# ProPrj___2025-07-17.net
KiCad netlist of a schematic drawn in EasyEDA Pro
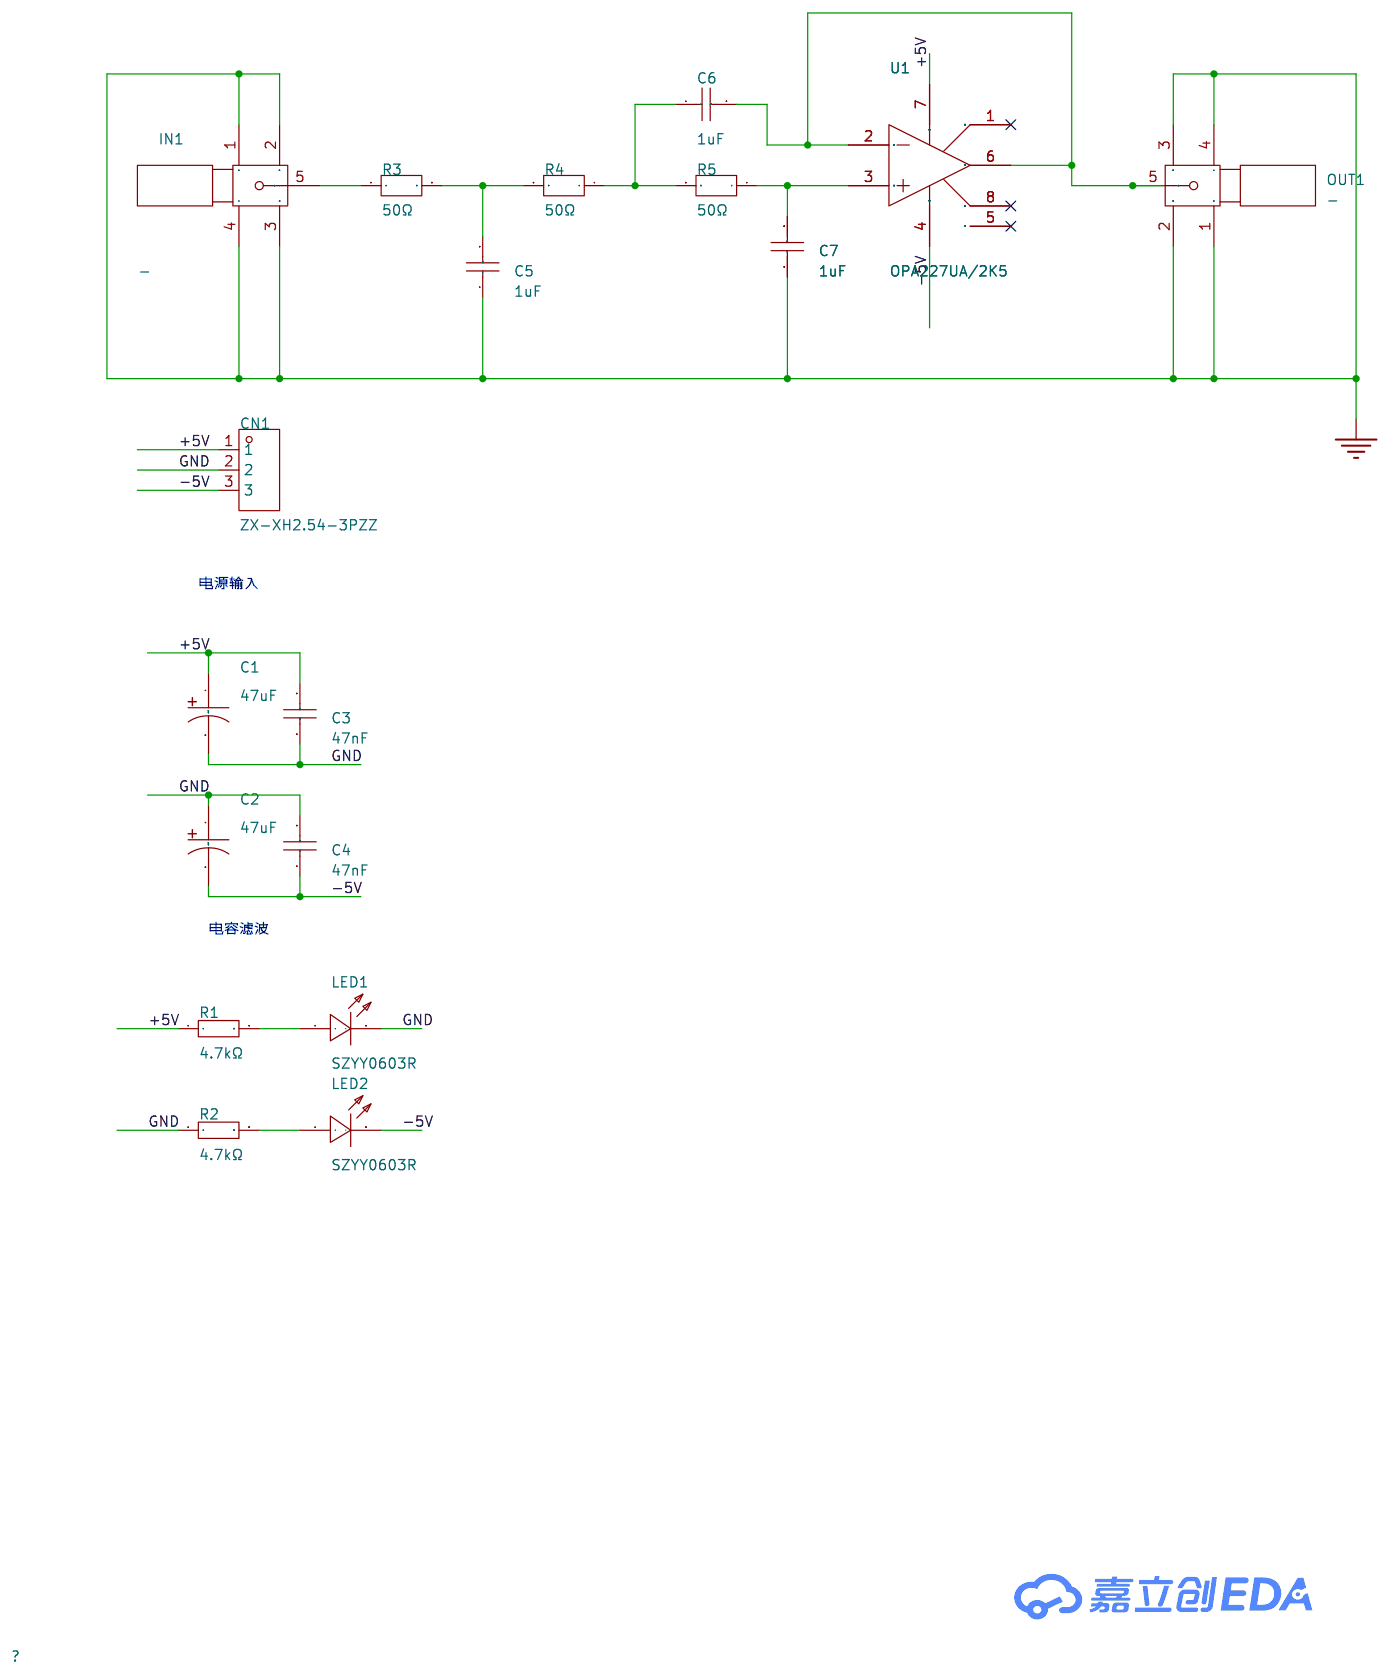
[diagram p0: schematic sheet]

(export (version "E")
  (design (tool "Eeschema 10.0.6"))
  (components
    (comp (ref "C1")
      (value "47uF")
      (footprint "easyedapro:CAP-TH_BD5.0-P2.00-D0.8-FD")
      (description "容值:47uF;精度:±20%;额定电压:25V;纹波电流:250mA@100kHz;等效串联电阻(ESR):300mΩ@100kHz;")
      (fields
        (field (name "Manufacturer Part") "NXB25V47M5*11 2.5TP")
        (field (name "Manufacturer") "SAMYOUNG(韩国三莹)")
      )
      (libsource (lib "easyedapro") (part "NXB25VB47M5*11_2.5TP"))
    )
    (comp (ref "C2")
      (value "47uF")
      (footprint "easyedapro:CAP-TH_BD5.0-P2.00-D0.8-FD")
      (description "容值:47uF;精度:±20%;额定电压:25V;纹波电流:250mA@100kHz;等效串联电阻(ESR):300mΩ@100kHz;")
      (fields
        (field (name "Manufacturer Part") "NXB25V47M5*11 2.5TP")
        (field (name "Manufacturer") "SAMYOUNG(韩国三莹)")
      )
      (libsource (lib "easyedapro") (part "NXB25VB47M5*11_2.5TP"))
    )
    (comp (ref "C3")
      (value "47nF")
      (footprint "easyedapro:C0805")
      (description "容值:47nF;精度:±10%;额定电压:50V;材质(温度系数):X7R;")
      (fields
        (field (name "Manufacturer Part") "CL21B473KBCNNNC")
        (field (name "Manufacturer") "SAMSUNG(三星)")
      )
      (libsource (lib "easyedapro") (part "CL21B473KBCNNNC"))
    )
    (comp (ref "C4")
      (value "47nF")
      (footprint "easyedapro:C0805")
      (description "容值:47nF;精度:±10%;额定电压:50V;材质(温度系数):X7R;")
      (fields
        (field (name "Manufacturer Part") "CL21B473KBCNNNC")
        (field (name "Manufacturer") "SAMSUNG(三星)")
      )
      (libsource (lib "easyedapro") (part "CL21B473KBCNNNC"))
    )
    (comp (ref "C5")
      (value "1uF")
      (footprint "easyedapro:C0805")
      (description "容值:1uF;精度:±10%;额定电压:50V;材质(温度系数):X7R;")
      (fields
        (field (name "Manufacturer Part") "CL21B105KBFNNNE")
        (field (name "Manufacturer") "SAMSUNG(三星)")
      )
      (libsource (lib "easyedapro") (part "CL21B105KBFNNNE"))
    )
    (comp (ref "C6")
      (value "1uF")
      (footprint "easyedapro:C0805")
      (description "容值:1uF;精度:±10%;额定电压:50V;材质(温度系数):X7R;")
      (fields
        (field (name "Manufacturer Part") "CL21B105KBFNNNE")
        (field (name "Manufacturer") "SAMSUNG(三星)")
      )
      (libsource (lib "easyedapro") (part "CL21B105KBFNNNE"))
    )
    (comp (ref "C7")
      (value "1uF")
      (footprint "easyedapro:C0805")
      (description "容值:1uF;精度:±10%;额定电压:50V;材质(温度系数):X7R;")
      (fields
        (field (name "Manufacturer Part") "CL21B105KBFNNNE")
        (field (name "Manufacturer") "SAMSUNG(三星)")
      )
      (libsource (lib "easyedapro") (part "CL21B105KBFNNNE"))
    )
    (comp (ref "CN1")
      (value "ZX-XH2.54-3PZZ")
      (footprint "easyedapro:CONN-TH_3P-P2.54_2501S-3P")
      (fields (field (name "Manufacturer") "Megastar(兆星)"))
      (libsource (lib "easyedapro") (part "ZX-XH2.54-3PZZ"))
    )
    (comp (ref "IN1")
      (value "-")
      (footprint "easyedapro:SMA-SMD_BWSMA-KE-P001")
      (description "连接器类型:板端;接口类型:内孔;端口数量:1;接口直径:5.2mm;接口长度/高度:-;频率:-;射频系列:SMA;阻抗:50Ω;样式:偏脚;工作温度:-;")
      (fields
        (field (name "Manufacturer Part") "BWSMA-KE-P001")
        (field (name "Manufacturer") "BAT WIRELESS(蝙蝠无线)")
      )
      (libsource (lib "easyedapro") (part "BWSMA-KE-P001"))
    )
    (comp (ref "LED1")
      (value "SZYY0603R")
      (footprint "easyedapro:LED0603-R-RD")
      (fields (field (name "Manufacturer") "yongyu(永裕光电)"))
      (libsource (lib "easyedapro") (part "SZYY0603R"))
    )
    (comp (ref "LED2")
      (value "SZYY0603R")
      (footprint "easyedapro:LED0603-R-RD")
      (fields (field (name "Manufacturer") "yongyu(永裕光电)"))
      (libsource (lib "easyedapro") (part "SZYY0603R"))
    )
    (comp (ref "OUT1")
      (value "-")
      (footprint "easyedapro:SMA-SMD_BWSMA-KE-P001")
      (description "连接器类型:板端;接口类型:内孔;端口数量:1;接口直径:5.2mm;接口长度/高度:-;频率:-;射频系列:SMA;阻抗:50Ω;样式:偏脚;工作温度:-;")
      (fields
        (field (name "Manufacturer Part") "BWSMA-KE-P001")
        (field (name "Manufacturer") "BAT WIRELESS(蝙蝠无线)")
      )
      (libsource (lib "easyedapro") (part "BWSMA-KE-P001"))
    )
    (comp (ref "R1")
      (value "4.7kΩ")
      (footprint "easyedapro:R0805")
      (description "电阻类型:厚膜电阻;阻值:4.7kΩ;精度:±1%;功率:125mW;最大工作电压:150V;温度系数:±100ppm/°C;")
      (fields
        (field (name "Manufacturer Part") "0805W8F4701T5E")
        (field (name "Manufacturer") "UNI-ROYAL(厚声)")
      )
      (libsource (lib "easyedapro") (part "0805W8F4701T5E"))
    )
    (comp (ref "R2")
      (value "4.7kΩ")
      (footprint "easyedapro:R0805")
      (description "电阻类型:厚膜电阻;阻值:4.7kΩ;精度:±1%;功率:125mW;最大工作电压:150V;温度系数:±100ppm/°C;")
      (fields
        (field (name "Manufacturer Part") "0805W8F4701T5E")
        (field (name "Manufacturer") "UNI-ROYAL(厚声)")
      )
      (libsource (lib "easyedapro") (part "0805W8F4701T5E"))
    )
    (comp (ref "R3")
      (value "50Ω")
      (footprint "easyedapro:R0805")
      (description "电阻类型:薄膜电阻;阻值:50Ω;精度:±0.1%;功率:100mW;温度系数:±25ppm/°C;")
      (fields (field (name "Manufacturer Part") "TD05G50R0BT") (field (name "Manufacturer") "FH(风华)"))
      (libsource (lib "easyedapro") (part "TD05G50R0BT"))
    )
    (comp (ref "R4")
      (value "50Ω")
      (footprint "easyedapro:R0805")
      (description "电阻类型:薄膜电阻;阻值:50Ω;精度:±0.1%;功率:100mW;温度系数:±25ppm/°C;")
      (fields (field (name "Manufacturer Part") "TD05G50R0BT") (field (name "Manufacturer") "FH(风华)"))
      (libsource (lib "easyedapro") (part "TD05G50R0BT"))
    )
    (comp (ref "R5")
      (value "50Ω")
      (footprint "easyedapro:R0805")
      (description "电阻类型:薄膜电阻;阻值:50Ω;精度:±0.1%;功率:100mW;温度系数:±25ppm/°C;")
      (fields (field (name "Manufacturer Part") "TD05G50R0BT") (field (name "Manufacturer") "FH(风华)"))
      (libsource (lib "easyedapro") (part "TD05G50R0BT"))
    )
    (comp (ref "U1")
      (value "OPA227UA/2K5")
      (footprint "easyedapro:SOIC-8_L4.9-W3.9-P1.27-LS6.0-BL")
      (description "放大器数:单路;增益带宽积(GBP):8MHz;输入偏置电流(Ib):2.5nA;压摆率(SR):2.3V/us;轨到轨:-;")
      (fields (field (name "Manufacturer") "TI(德州仪器)"))
      (libsource (lib "easyedapro") (part "OPA227UA/2K5"))
    )
  )
  (nets
    (net (code "1") (name "/+5V") (class "Default")
      (node (ref "C1") (pin "1") (pinfunction "1_1") (pintype "unspecified"))
      (node (ref "C3") (pin "2") (pinfunction "2_2") (pintype "input"))
      (node (ref "CN1") (pin "1") (pinfunction "1_1") (pintype "unspecified"))
      (node (ref "R1") (pin "1") (pinfunction "1_1") (pintype "input"))
      (node (ref "U1") (pin "7") (pinfunction "VCC_7") (pintype "unspecified"))
    )
    (net (code "2") (name "/-5V") (class "Default")
      (node (ref "C2") (pin "2") (pinfunction "2_2") (pintype "unspecified"))
      (node (ref "C4") (pin "1") (pinfunction "1_1") (pintype "input"))
      (node (ref "CN1") (pin "3") (pinfunction "3_3") (pintype "unspecified"))
      (node (ref "LED2") (pin "2") (pinfunction "-_2") (pintype "unspecified"))
      (node (ref "U1") (pin "4") (pinfunction "VSS_4") (pintype "unspecified"))
    )
    (net (code "3") (name "GND") (class "Default")
      (node (ref "C1") (pin "2") (pinfunction "2_2") (pintype "unspecified"))
      (node (ref "C2") (pin "1") (pinfunction "1_1") (pintype "unspecified"))
      (node (ref "C3") (pin "1") (pinfunction "1_1") (pintype "input"))
      (node (ref "C4") (pin "2") (pinfunction "2_2") (pintype "input"))
      (node (ref "C5") (pin "1") (pinfunction "1_1") (pintype "input"))
      (node (ref "C7") (pin "1") (pinfunction "1_1") (pintype "input"))
      (node (ref "CN1") (pin "2") (pinfunction "2_2") (pintype "unspecified"))
      (node (ref "IN1") (pin "1") (pinfunction "1_1") (pintype "unspecified"))
      (node (ref "IN1") (pin "2") (pinfunction "2_2") (pintype "unspecified"))
      (node (ref "IN1") (pin "3") (pinfunction "3_3") (pintype "unspecified"))
      (node (ref "IN1") (pin "4") (pinfunction "4_4") (pintype "unspecified"))
      (node (ref "LED1") (pin "2") (pinfunction "-_2") (pintype "unspecified"))
      (node (ref "OUT1") (pin "1") (pinfunction "1_1") (pintype "unspecified"))
      (node (ref "OUT1") (pin "2") (pinfunction "2_2") (pintype "unspecified"))
      (node (ref "OUT1") (pin "3") (pinfunction "3_3") (pintype "unspecified"))
      (node (ref "OUT1") (pin "4") (pinfunction "4_4") (pintype "unspecified"))
      (node (ref "R2") (pin "1") (pinfunction "1_1") (pintype "input"))
    )
    (net (code "4") (name "Net-(C5-Pad2)") (class "Default")
      (node (ref "C5") (pin "2") (pinfunction "2_2") (pintype "input"))
      (node (ref "R3") (pin "2") (pinfunction "2_2") (pintype "unspecified"))
      (node (ref "R4") (pin "2") (pinfunction "2_2") (pintype "unspecified"))
    )
    (net (code "5") (name "Net-(C6-Pad1)") (class "Default")
      (node (ref "C6") (pin "1") (pinfunction "1_1") (pintype "input"))
      (node (ref "R4") (pin "1") (pinfunction "1_1") (pintype "unspecified"))
      (node (ref "R5") (pin "2") (pinfunction "2_2") (pintype "unspecified"))
    )
    (net (code "6") (name "Net-(IN1-Pad5)") (class "Default")
      (node (ref "IN1") (pin "5") (pinfunction "5_5") (pintype "unspecified"))
      (node (ref "R3") (pin "1") (pinfunction "1_1") (pintype "unspecified"))
    )
    (net (code "7") (name "Net-(LED1-+)") (class "Default")
      (node (ref "LED1") (pin "1") (pinfunction "+_1") (pintype "unspecified"))
      (node (ref "R1") (pin "2") (pinfunction "2_2") (pintype "input"))
    )
    (net (code "8") (name "Net-(LED2-+)") (class "Default")
      (node (ref "LED2") (pin "1") (pinfunction "+_1") (pintype "unspecified"))
      (node (ref "R2") (pin "2") (pinfunction "2_2") (pintype "input"))
    )
    (net (code "9") (name "Net-(U1-OUT)") (class "Default")
      (node (ref "C6") (pin "2") (pinfunction "2_2") (pintype "input"))
      (node (ref "OUT1") (pin "5") (pinfunction "5_5") (pintype "unspecified"))
      (node (ref "U1") (pin "2") (pinfunction "VIN-_2") (pintype "unspecified"))
      (node (ref "U1") (pin "6") (pinfunction "OUT_6") (pintype "output"))
    )
    (net (code "10") (name "Net-(U1-VIN+)") (class "Default")
      (node (ref "C7") (pin "2") (pinfunction "2_2") (pintype "input"))
      (node (ref "R5") (pin "1") (pinfunction "1_1") (pintype "unspecified"))
      (node (ref "U1") (pin "3") (pinfunction "VIN+_3") (pintype "unspecified"))
    )
    (net (code "11") (name "unconnected-(U1-NC-Pad5)") (class "Default")
      (node (ref "U1") (pin "5") (pinfunction "NC_5") (pintype "unspecified+no_connect"))
    )
    (net (code "12") (name "unconnected-(U1-TRIM-Pad1)") (class "Default")
      (node (ref "U1") (pin "1") (pinfunction "TRIM_1") (pintype "unspecified+no_connect"))
    )
    (net (code "13") (name "unconnected-(U1-TRIM-Pad8)") (class "Default")
      (node (ref "U1") (pin "8") (pinfunction "TRIM_8") (pintype "unspecified+no_connect"))
    )
  )
)
